# power_sup.net
KiCad netlist of a schematic drawn in Altium Designer
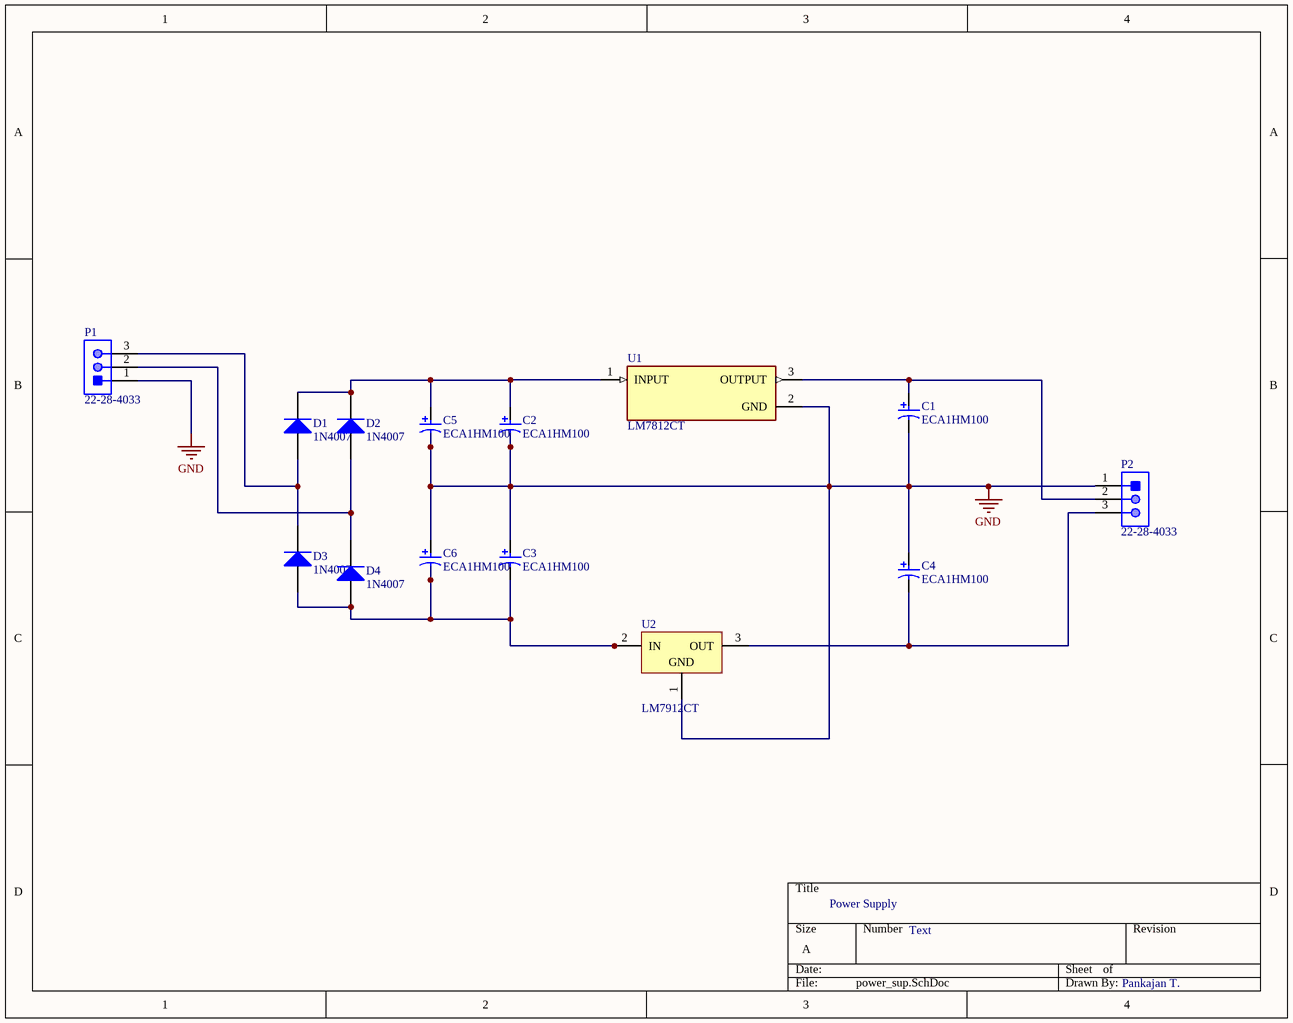
[diagram p0: power_sup.SchDoc]

(export (version "E")
  (design (tool "Eeschema 10.0.6"))
  (components
    (comp (ref "C1")
      (value "ECA1HM100")
      (footprint "CAPPR55-200-1100X500X1200")
      (description "Aluminum Electrolytic Capacitor, 10 uF, +/- 20%, 50 V, -40 to 85 degC, 2-Pin THD, RoHS, Bulk")
      (fields (field (name "MANUFACTURER") "Panasonic") (field (name "TOLERANCE") "20%"))
      (libsource (lib "Altium Content Vault") (part "CAP-P-2"))
    )
    (comp (ref "C2")
      (value "ECA1HM100")
      (footprint "CAPPR55-200-1100X500X1200")
      (description "Aluminum Electrolytic Capacitor, 10 uF, +/- 20%, 50 V, -40 to 85 degC, 2-Pin THD, RoHS, Bulk")
      (fields (field (name "MANUFACTURER") "Panasonic") (field (name "TOLERANCE") "20%"))
      (libsource (lib "Altium Content Vault") (part "CAP-P-2"))
    )
    (comp (ref "C3")
      (value "ECA1HM100")
      (footprint "CAPPR55-200-1100X500X1200")
      (description "Aluminum Electrolytic Capacitor, 10 uF, +/- 20%, 50 V, -40 to 85 degC, 2-Pin THD, RoHS, Bulk")
      (fields (field (name "MANUFACTURER") "Panasonic") (field (name "TOLERANCE") "20%"))
      (libsource (lib "Altium Content Vault") (part "CAP-P-2"))
    )
    (comp (ref "C4")
      (value "ECA1HM100")
      (footprint "CAPPR55-200-1100X500X1200")
      (description "Aluminum Electrolytic Capacitor, 10 uF, +/- 20%, 50 V, -40 to 85 degC, 2-Pin THD, RoHS, Bulk")
      (fields (field (name "MANUFACTURER") "Panasonic") (field (name "TOLERANCE") "20%"))
      (libsource (lib "Altium Content Vault") (part "CAP-P-2"))
    )
    (comp (ref "C5")
      (value "ECA1HM100")
      (footprint "CAPPR55-200-1100X500X1200")
      (description "Aluminum Electrolytic Capacitor, 10 uF, +/- 20%, 50 V, -40 to 85 degC, 2-Pin THD, RoHS, Bulk")
      (fields (field (name "MANUFACTURER") "Panasonic") (field (name "TOLERANCE") "20%"))
      (libsource (lib "Altium Content Vault") (part "CAP-P-2"))
    )
    (comp (ref "C6")
      (value "ECA1HM100")
      (footprint "CAPPR55-200-1100X500X1200")
      (description "Aluminum Electrolytic Capacitor, 10 uF, +/- 20%, 50 V, -40 to 85 degC, 2-Pin THD, RoHS, Bulk")
      (fields (field (name "MANUFACTURER") "Panasonic") (field (name "TOLERANCE") "20%"))
      (libsource (lib "Altium Content Vault") (part "CAP-P-2"))
    )
    (comp (ref "D1")
      (value "1N4007")
      (footprint "FAIR-DO-41-2")
      (description "General Purpose Rectifier, 1.1 V, 1.0 A, -55 to 175 degC, 2-Pin DO-41, RoHS, Tape and Reel")
      (fields (field (name "MANUFACTURER") "Fairchild"))
      (libsource (lib "workplace") (part "KESE-D_K1A2-2"))
    )
    (comp (ref "D2")
      (value "1N4007")
      (footprint "FAIR-DO-41-2")
      (description "General Purpose Rectifier, 1.1 V, 1.0 A, -55 to 175 degC, 2-Pin DO-41, RoHS, Tape and Reel")
      (fields (field (name "MANUFACTURER") "Fairchild"))
      (libsource (lib "workplace") (part "KESE-D_K1A2-2"))
    )
    (comp (ref "D3")
      (value "1N4007")
      (footprint "FAIR-DO-41-2")
      (description "General Purpose Rectifier, 1.1 V, 1.0 A, -55 to 175 degC, 2-Pin DO-41, RoHS, Tape and Reel")
      (fields (field (name "MANUFACTURER") "Fairchild"))
      (libsource (lib "workplace") (part "KESE-D_K1A2-2"))
    )
    (comp (ref "D4")
      (value "1N4007")
      (footprint "FAIR-DO-41-2")
      (description "General Purpose Rectifier, 1.1 V, 1.0 A, -55 to 175 degC, 2-Pin DO-41, RoHS, Tape and Reel")
      (fields (field (name "MANUFACTURER") "Fairchild"))
      (libsource (lib "workplace") (part "KESE-D_K1A2-2"))
    )
    (comp (ref "P1")
      (value "22-28-4033")
      (footprint "MOLX-22-28-4033_V")
      (description "Male Header, Pitch 2.54 mm, 1 x 3 Position, Height 8.38 mm, Tail Length 3.18 mm, RoHS, Bulk")
      (fields (field (name "MANUFACTURER") "Molex"))
      (libsource (lib "") (part "CN-1P-M-R3_1"))
    )
    (comp (ref "P2")
      (value "22-28-4033")
      (footprint "MOLX-22-28-4033_V")
      (description "Male Header, Pitch 2.54 mm, 1 x 3 Position, Height 8.38 mm, Tail Length 3.18 mm, RoHS, Bulk")
      (fields (field (name "MANUFACTURER") "Molex"))
      (libsource (lib "Altium Content Vault") (part "CN-1P-M-R3"))
    )
    (comp (ref "U1")
      (value "LM7812CT")
      (footprint "FP-TO220B03-MFG")
      (description "IC REG LINEAR 12V 1A TO220-3")
      (fields
        (field (name "OCTOPART") "https://octopart.com/lm7812ct-on+semiconductor-14383031")
        (field (name "OBSOLETE PART") "true")
      )
      (libsource (lib "Altium Content Vault") (part "6207a8f1a6b4db326a9e0a8a99b4969"))
    )
    (comp (ref "U2")
      (value "LM7912CT")
      (footprint "NDE0003A")
      (description "3-Terminal Negative Regulator, 3-pin TO-220")
      (fields (field (name "MANUFACTURER") "Texas Instruments"))
      (libsource (lib "Altium Content Vault") (part "PM-REG-LM7905-SIL3"))
    )
  )
  (nets
    (net (code "1") (name "GND") (class "Default")
      (node (ref "C1") (pin "2") (pinfunction "2_2") (pintype "passive"))
      (node (ref "C2") (pin "2") (pinfunction "2_2") (pintype "passive"))
      (node (ref "C3") (pin "1") (pinfunction "1_1") (pintype "passive"))
      (node (ref "C4") (pin "1") (pinfunction "1_1") (pintype "passive"))
      (node (ref "C5") (pin "2") (pinfunction "2_2") (pintype "passive"))
      (node (ref "C6") (pin "1") (pinfunction "1_1") (pintype "passive"))
      (node (ref "P1") (pin "1") (pinfunction "1_1") (pintype "passive"))
      (node (ref "P2") (pin "1") (pinfunction "1_1") (pintype "passive"))
      (node (ref "U1") (pin "2") (pinfunction "GND_2") (pintype "power_in"))
      (node (ref "U2") (pin "1") (pinfunction "GND_1") (pintype "power_in"))
    )
    (net (code "2") (name "Net-(D1-A)") (class "Default")
      (node (ref "D1") (pin "2") (pinfunction "A_2") (pintype "passive"))
      (node (ref "D3") (pin "1") (pinfunction "K_1") (pintype "passive"))
      (node (ref "P1") (pin "3") (pinfunction "3_3") (pintype "passive"))
    )
    (net (code "3") (name "Net-(D1-K)") (class "Default")
      (node (ref "C2") (pin "1") (pinfunction "1_1") (pintype "passive"))
      (node (ref "C5") (pin "1") (pinfunction "1_1") (pintype "passive"))
      (node (ref "D1") (pin "1") (pinfunction "K_1") (pintype "passive"))
      (node (ref "D2") (pin "1") (pinfunction "K_1") (pintype "passive"))
      (node (ref "U1") (pin "1") (pinfunction "INPUT_1") (pintype "input"))
    )
    (net (code "4") (name "Net-(D2-A)") (class "Default")
      (node (ref "D2") (pin "2") (pinfunction "A_2") (pintype "passive"))
      (node (ref "D4") (pin "1") (pinfunction "K_1") (pintype "passive"))
      (node (ref "P1") (pin "2") (pinfunction "2_2") (pintype "passive"))
    )
    (net (code "5") (name "Net-(D3-A)") (class "Default")
      (node (ref "C3") (pin "2") (pinfunction "2_2") (pintype "passive"))
      (node (ref "C6") (pin "2") (pinfunction "2_2") (pintype "passive"))
      (node (ref "D3") (pin "2") (pinfunction "A_2") (pintype "passive"))
      (node (ref "D4") (pin "2") (pinfunction "A_2") (pintype "passive"))
      (node (ref "U2") (pin "2") (pinfunction "IN_2") (pintype "power_in"))
    )
    (net (code "6") (name "Net-(U1-OUTPUT)") (class "Default")
      (node (ref "C1") (pin "1") (pinfunction "1_1") (pintype "passive"))
      (node (ref "P2") (pin "2") (pinfunction "2_2") (pintype "passive"))
      (node (ref "U1") (pin "3") (pinfunction "OUTPUT_3") (pintype "output"))
    )
    (net (code "7") (name "Net-(U2-OUT)") (class "Default")
      (node (ref "C4") (pin "2") (pinfunction "2_2") (pintype "passive"))
      (node (ref "P2") (pin "3") (pinfunction "3_3") (pintype "passive"))
      (node (ref "U2") (pin "3") (pinfunction "OUT_3") (pintype "power_in"))
    )
  )
)
